# TwinklingPendant.net
KiCad netlist of a schematic drawn in EAGLE
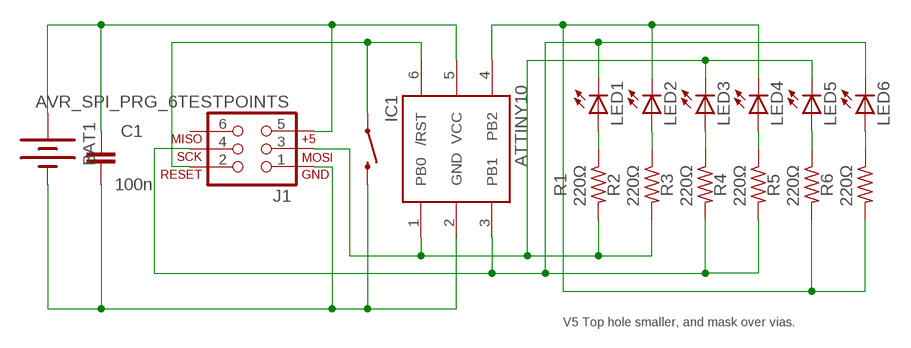
[diagram p0: schematic, sheet 1]

(export (version "E")
  (design (tool "Eeschema 10.0.6"))
  (components
    (comp (ref "BAT1")
      (value "BATTERY12MM")
      (footprint "eagle-import:BATTCON_12MM")
      (libsource (lib "eagle-import") (part "BATTERY12MM"))
    )
    (comp (ref "C1")
      (value "100n")
      (footprint "eagle-import:0603-CAP")
      (libsource (lib "eagle-import") (part "CAP0603-CAP"))
    )
    (comp (ref "IC1")
      (value "ATTINY10")
      (footprint "eagle-import:SOT23-6")
      (libsource (lib "eagle-import") (part "ATTINY10"))
    )
    (comp (ref "J1")
      (value "AVR_SPI_PRG_6TESTPOINTS")
      (footprint "eagle-import:2X3_TEST_POINTS")
      (libsource (lib "eagle-import") (part "AVR_SPI_PRG_6TESTPOINTS"))
    )
    (comp (ref "LED1")
      (value "LEDCHIPLED_0805")
      (footprint "eagle-import:CHIPLED_0805")
      (libsource (lib "eagle-import") (part "LEDCHIPLED_0805"))
    )
    (comp (ref "LED2")
      (value "LEDCHIPLED_0805")
      (footprint "eagle-import:CHIPLED_0805")
      (libsource (lib "eagle-import") (part "LEDCHIPLED_0805"))
    )
    (comp (ref "LED3")
      (value "LEDCHIPLED_0805")
      (footprint "eagle-import:CHIPLED_0805")
      (libsource (lib "eagle-import") (part "LEDCHIPLED_0805"))
    )
    (comp (ref "LED4")
      (value "LEDCHIPLED_0805")
      (footprint "eagle-import:CHIPLED_0805")
      (libsource (lib "eagle-import") (part "LEDCHIPLED_0805"))
    )
    (comp (ref "LED5")
      (value "LEDCHIPLED_0805")
      (footprint "eagle-import:CHIPLED_0805")
      (libsource (lib "eagle-import") (part "LEDCHIPLED_0805"))
    )
    (comp (ref "LED6")
      (value "LEDCHIPLED_0805")
      (footprint "eagle-import:CHIPLED_0805")
      (libsource (lib "eagle-import") (part "LEDCHIPLED_0805"))
    )
    (comp (ref "R1")
      (value "220Ω")
      (footprint "eagle-import:R0805")
      (libsource (lib "eagle-import") (part "R-US_R0805"))
    )
    (comp (ref "R2")
      (value "220Ω")
      (footprint "eagle-import:R0805")
      (libsource (lib "eagle-import") (part "R-US_R0805"))
    )
    (comp (ref "R3")
      (value "220Ω")
      (footprint "eagle-import:R0805")
      (libsource (lib "eagle-import") (part "R-US_R0805"))
    )
    (comp (ref "R4")
      (value "220Ω")
      (footprint "eagle-import:R0805")
      (libsource (lib "eagle-import") (part "R-US_R0805"))
    )
    (comp (ref "R5")
      (value "220Ω")
      (footprint "eagle-import:R0805")
      (libsource (lib "eagle-import") (part "R-US_R0805"))
    )
    (comp (ref "R6")
      (value "220Ω")
      (footprint "eagle-import:R0805")
      (libsource (lib "eagle-import") (part "R-US_R0805"))
    )
    (comp (ref "S2")
      (value "SWITCH-MOMENTARY-2SMD")
      (footprint "eagle-import:TACTILE-SWITCH-SMD")
      (libsource (lib "eagle-import") (part "SWITCH-MOMENTARY-2SMD"))
    )
  )
  (nets
    (net (code "1") (name "Net-(BAT1-+)") (class "Default")
      (node (ref "BAT1") (pin "PWR@1") (pinfunction "+_PWR@1") (pintype "power_in"))
      (node (ref "C1") (pin "1") (pinfunction "1_1") (pintype "passive"))
      (node (ref "IC1") (pin "5") (pinfunction "VCC_5") (pintype "power_in"))
      (node (ref "J1") (pin "5") (pinfunction "5_5") (pintype "passive"))
    )
    (net (code "2") (name "Net-(BAT1--)") (class "Default")
      (node (ref "BAT1") (pin "GND") (pinfunction "-_GND") (pintype "power_in"))
      (node (ref "C1") (pin "2") (pinfunction "2_2") (pintype "passive"))
      (node (ref "IC1") (pin "2") (pinfunction "GND_2") (pintype "power_in"))
      (node (ref "J1") (pin "1") (pinfunction "1_1") (pintype "passive"))
      (node (ref "S2") (pin "3") (pinfunction "2_3") (pintype "passive"))
    )
    (net (code "3") (name "Net-(IC1-PB0)") (class "Default")
      (node (ref "IC1") (pin "1") (pinfunction "PB0_1") (pintype "bidirectional"))
      (node (ref "J1") (pin "3") (pinfunction "3_3") (pintype "passive"))
      (node (ref "LED3") (pin "C") (pinfunction "C_C") (pintype "passive"))
      (node (ref "LED5") (pin "C") (pinfunction "C_C") (pintype "passive"))
      (node (ref "R1") (pin "2") (pinfunction "2_2") (pintype "passive"))
      (node (ref "R2") (pin "2") (pinfunction "2_2") (pintype "passive"))
    )
    (net (code "4") (name "Net-(IC1-PB1)") (class "Default")
      (node (ref "IC1") (pin "3") (pinfunction "PB1_3") (pintype "bidirectional"))
      (node (ref "J1") (pin "4") (pinfunction "4_4") (pintype "passive"))
      (node (ref "LED1") (pin "C") (pinfunction "C_C") (pintype "passive"))
      (node (ref "LED6") (pin "C") (pinfunction "C_C") (pintype "passive"))
      (node (ref "R3") (pin "2") (pinfunction "2_2") (pintype "passive"))
      (node (ref "R4") (pin "2") (pinfunction "2_2") (pintype "passive"))
    )
    (net (code "5") (name "Net-(IC1-PB2)") (class "Default")
      (node (ref "IC1") (pin "4") (pinfunction "PB2_4") (pintype "bidirectional"))
      (node (ref "LED2") (pin "C") (pinfunction "C_C") (pintype "passive"))
      (node (ref "LED4") (pin "C") (pinfunction "C_C") (pintype "passive"))
      (node (ref "R5") (pin "2") (pinfunction "2_2") (pintype "passive"))
      (node (ref "R6") (pin "2") (pinfunction "2_2") (pintype "passive"))
    )
    (net (code "6") (name "Net-(IC1-{slash}RST)") (class "Default")
      (node (ref "IC1") (pin "6") (pinfunction "/RST_6") (pintype "bidirectional"))
      (node (ref "J1") (pin "2") (pinfunction "2_2") (pintype "passive"))
      (node (ref "S2") (pin "1") (pinfunction "1_1") (pintype "passive"))
    )
    (net (code "7") (name "Net-(LED1-PadA)") (class "Default")
      (node (ref "LED1") (pin "A") (pinfunction "A_A") (pintype "passive"))
      (node (ref "R1") (pin "1") (pinfunction "1_1") (pintype "passive"))
    )
    (net (code "8") (name "Net-(LED2-PadA)") (class "Default")
      (node (ref "LED2") (pin "A") (pinfunction "A_A") (pintype "passive"))
      (node (ref "R2") (pin "1") (pinfunction "1_1") (pintype "passive"))
    )
    (net (code "9") (name "Net-(LED3-PadA)") (class "Default")
      (node (ref "LED3") (pin "A") (pinfunction "A_A") (pintype "passive"))
      (node (ref "R3") (pin "1") (pinfunction "1_1") (pintype "passive"))
    )
    (net (code "10") (name "Net-(LED4-PadA)") (class "Default")
      (node (ref "LED4") (pin "A") (pinfunction "A_A") (pintype "passive"))
      (node (ref "R4") (pin "1") (pinfunction "1_1") (pintype "passive"))
    )
    (net (code "11") (name "Net-(LED5-PadA)") (class "Default")
      (node (ref "LED5") (pin "A") (pinfunction "A_A") (pintype "passive"))
      (node (ref "R5") (pin "1") (pinfunction "1_1") (pintype "passive"))
    )
    (net (code "12") (name "Net-(LED6-PadA)") (class "Default")
      (node (ref "LED6") (pin "A") (pinfunction "A_A") (pintype "passive"))
      (node (ref "R6") (pin "1") (pinfunction "1_1") (pintype "passive"))
    )
    (net (code "13") (name "unconnected-(J1-Pad6)") (class "Default")
      (node (ref "J1") (pin "6") (pinfunction "6_6") (pintype "passive"))
    )
  )
)
